# board-alt.net
KiCad netlist of a schematic drawn in EAGLE
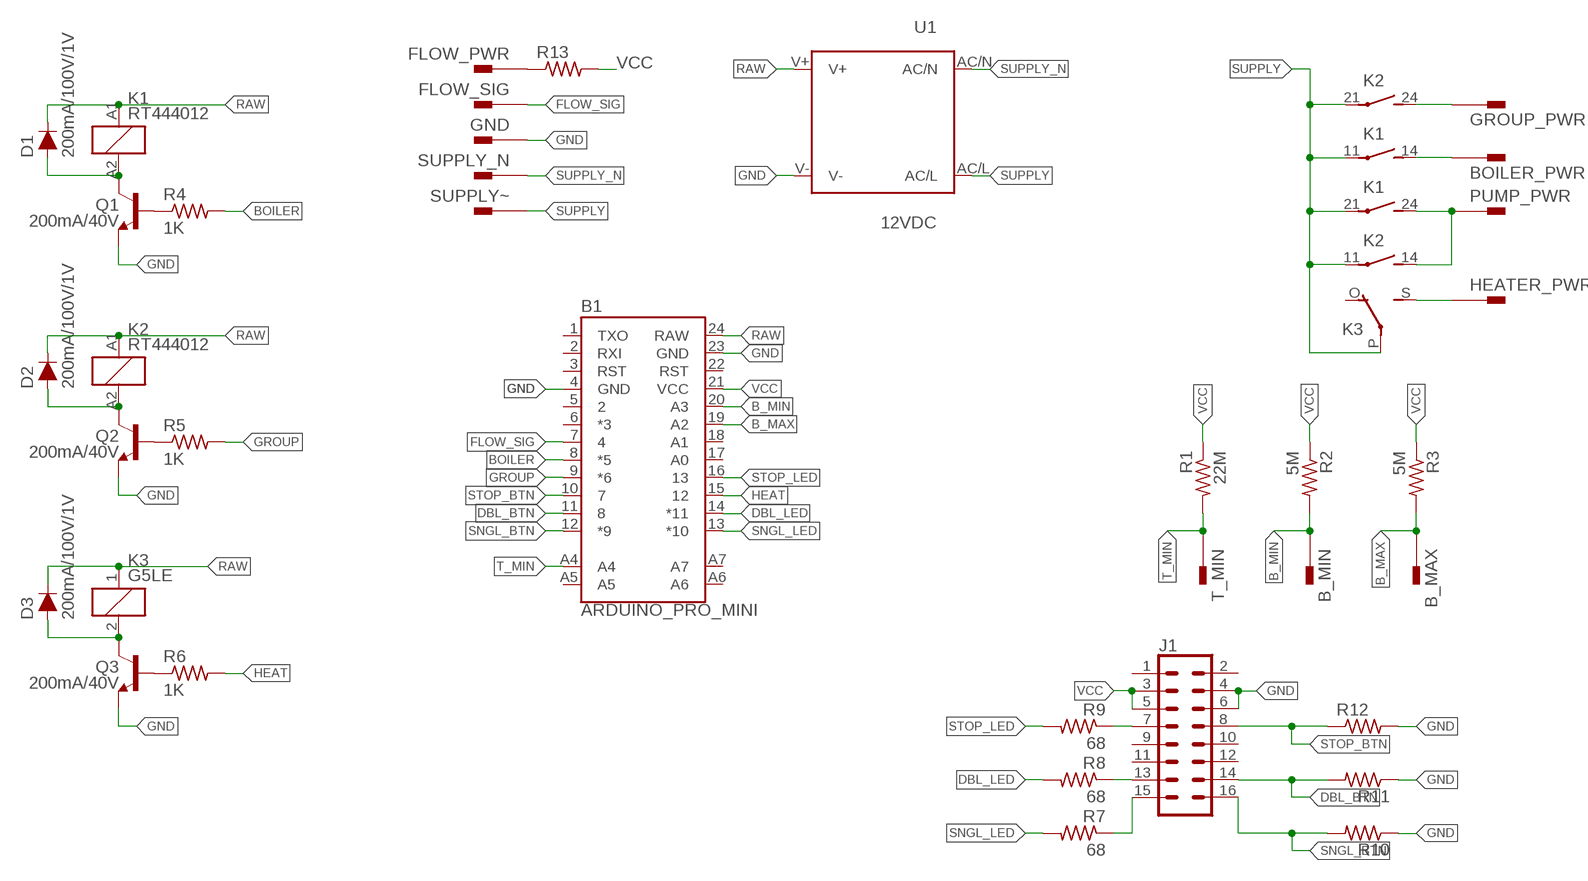
[diagram p0: schematic, sheet 1]

(export (version "E")
  (design (tool "Eeschema 10.0.6"))
  (components
    (comp (ref "B1")
      (value "ARDUINO_PRO_MINI")
      (footprint "eagle-import:ARDUINO_PRO_MINI")
      (libsource (lib "eagle-import") (part "ARDUINO_PRO_MINI"))
    )
    (comp (ref "BOILER_PWR")
      (value "PIN2F061.040")
      (footprint "eagle-import:F061.040")
      (libsource (lib "eagle-import") (part "PIN2F061.040"))
    )
    (comp (ref "B_MAX")
      (value "PIN2F061.040")
      (footprint "eagle-import:F061.040")
      (libsource (lib "eagle-import") (part "PIN2F061.040"))
    )
    (comp (ref "B_MIN")
      (value "PIN2F061.040")
      (footprint "eagle-import:F061.040")
      (libsource (lib "eagle-import") (part "PIN2F061.040"))
    )
    (comp (ref "D1")
      (value "200mA/100V/1V")
      (footprint "eagle-import:DIODE-1N4148")
      (libsource (lib "eagle-import") (part "DIODE-1N4148"))
    )
    (comp (ref "D2")
      (value "200mA/100V/1V")
      (footprint "eagle-import:DIODE-1N4148")
      (libsource (lib "eagle-import") (part "DIODE-1N4148"))
    )
    (comp (ref "D3")
      (value "200mA/100V/1V")
      (footprint "eagle-import:DIODE-1N4148")
      (libsource (lib "eagle-import") (part "DIODE-1N4148"))
    )
    (comp (ref "FLOW_PWR")
      (value "PIN2F061.040")
      (footprint "eagle-import:F061.040")
      (libsource (lib "eagle-import") (part "PIN2F061.040"))
    )
    (comp (ref "FLOW_SIG")
      (value "PIN2F061.040")
      (footprint "eagle-import:F061.040")
      (libsource (lib "eagle-import") (part "PIN2F061.040"))
    )
    (comp (ref "GND")
      (value "PIN2F061.040")
      (footprint "eagle-import:F061.040")
      (libsource (lib "eagle-import") (part "PIN2F061.040"))
    )
    (comp (ref "GROUP_PWR")
      (value "PIN2F061.040")
      (footprint "eagle-import:F061.040")
      (libsource (lib "eagle-import") (part "PIN2F061.040"))
    )
    (comp (ref "HEATER_PWR")
      (value "PIN2F061.040")
      (footprint "eagle-import:F061.040")
      (libsource (lib "eagle-import") (part "PIN2F061.040"))
    )
    (comp (ref "J1")
      (value "CONN_08X2")
      (footprint "eagle-import:2X8")
      (libsource (lib "eagle-import") (part "CONN_08X2"))
    )
    (comp (ref "K1")
      (value "RT444012")
      (footprint "eagle-import:RT2N_O")
      (libsource (lib "eagle-import") (part "RT44?4012"))
    )
    (comp (ref "K2")
      (value "RT444012")
      (footprint "eagle-import:RT2N_O")
      (libsource (lib "eagle-import") (part "RT44?4012"))
    )
    (comp (ref "K3")
      (value "G5LE")
      (footprint "eagle-import:G5LE")
      (libsource (lib "eagle-import") (part "G5LE"))
    )
    (comp (ref "PUMP_PWR")
      (value "PIN2F061.040")
      (footprint "eagle-import:F061.040")
      (libsource (lib "eagle-import") (part "PIN2F061.040"))
    )
    (comp (ref "Q1")
      (value "200mA/40V")
      (footprint "eagle-import:TO-92")
      (libsource (lib "eagle-import") (part "TRANS_NPN-2N3904"))
    )
    (comp (ref "Q2")
      (value "200mA/40V")
      (footprint "eagle-import:TO-92")
      (libsource (lib "eagle-import") (part "TRANS_NPN-2N3904"))
    )
    (comp (ref "Q3")
      (value "200mA/40V")
      (footprint "eagle-import:TO-92")
      (libsource (lib "eagle-import") (part "TRANS_NPN-2N3904"))
    )
    (comp (ref "R1")
      (value "22M")
      (footprint "eagle-import:0207_7")
      (libsource (lib "eagle-import") (part "R-US_0207/7"))
    )
    (comp (ref "R2")
      (value "5M")
      (footprint "eagle-import:0207_7")
      (libsource (lib "eagle-import") (part "R-US_0207/7"))
    )
    (comp (ref "R3")
      (value "5M")
      (footprint "eagle-import:0207_7")
      (libsource (lib "eagle-import") (part "R-US_0207/7"))
    )
    (comp (ref "R4")
      (value "1K")
      (footprint "eagle-import:0207_7")
      (libsource (lib "eagle-import") (part "R-US_0207/7"))
    )
    (comp (ref "R5")
      (value "1K")
      (footprint "eagle-import:0207_7")
      (libsource (lib "eagle-import") (part "R-US_0207/7"))
    )
    (comp (ref "R6")
      (value "1K")
      (footprint "eagle-import:0207_7")
      (libsource (lib "eagle-import") (part "R-US_0207/7"))
    )
    (comp (ref "R7")
      (value "68")
      (footprint "eagle-import:0207_7")
      (libsource (lib "eagle-import") (part "R-US_0207/7"))
    )
    (comp (ref "R8")
      (value "68")
      (footprint "eagle-import:0207_7")
      (libsource (lib "eagle-import") (part "R-US_0207/7"))
    )
    (comp (ref "R9")
      (value "68")
      (footprint "eagle-import:0207_7")
      (libsource (lib "eagle-import") (part "R-US_0207/7"))
    )
    (comp (ref "R10")
      (value "R-US_0207/7")
      (footprint "eagle-import:0207_7")
      (libsource (lib "eagle-import") (part "R-US_0207/7"))
    )
    (comp (ref "R11")
      (value "R-US_0207/7")
      (footprint "eagle-import:0207_7")
      (libsource (lib "eagle-import") (part "R-US_0207/7"))
    )
    (comp (ref "R12")
      (value "R-US_0207/7")
      (footprint "eagle-import:0207_7")
      (libsource (lib "eagle-import") (part "R-US_0207/7"))
    )
    (comp (ref "R13")
      (value "R-US_0207/7")
      (footprint "eagle-import:0207_7")
      (libsource (lib "eagle-import") (part "R-US_0207/7"))
    )
    (comp (ref "SUPPLY_N")
      (value "PIN2F061.040")
      (footprint "eagle-import:F061.040")
      (libsource (lib "eagle-import") (part "PIN2F061.040"))
    )
    (comp (ref "SUPPLY~")
      (value "PIN2F061.040")
      (footprint "eagle-import:F061.040")
      (libsource (lib "eagle-import") (part "PIN2F061.040"))
    )
    (comp (ref "T_MIN")
      (value "PIN2F061.040")
      (footprint "eagle-import:F061.040")
      (libsource (lib "eagle-import") (part "PIN2F061.040"))
    )
    (comp (ref "U1")
      (value "12VDC")
      (footprint "eagle-import:IRM_05_10")
      (libsource (lib "eagle-import") (part "IRM_05/10"))
    )
  )
  (nets
    (net (code "1") (name "BOILER") (class "Default")
      (node (ref "B1") (pin "8") (pinfunction "*5_8") (pintype "bidirectional"))
      (node (ref "R4") (pin "2") (pinfunction "2_2") (pintype "passive"))
    )
    (net (code "2") (name "B_MAX") (class "Default")
      (node (ref "B1") (pin "19") (pinfunction "A2_19") (pintype "bidirectional"))
      (node (ref "B_MAX") (pin "A1") (pinfunction "1_A1") (pintype "passive"))
      (node (ref "B_MAX") (pin "A2") (pinfunction "1_A2") (pintype "passive"))
      (node (ref "R3") (pin "2") (pinfunction "2_2") (pintype "passive"))
    )
    (net (code "3") (name "B_MIN") (class "Default")
      (node (ref "B1") (pin "20") (pinfunction "A3_20") (pintype "bidirectional"))
      (node (ref "B_MIN") (pin "A1") (pinfunction "1_A1") (pintype "passive"))
      (node (ref "B_MIN") (pin "A2") (pinfunction "1_A2") (pintype "passive"))
      (node (ref "R2") (pin "2") (pinfunction "2_2") (pintype "passive"))
    )
    (net (code "4") (name "DBL_BTN") (class "Default")
      (node (ref "B1") (pin "11") (pinfunction "8_11") (pintype "bidirectional"))
      (node (ref "J1") (pin "14") (pinfunction "14_14") (pintype "passive"))
      (node (ref "R11") (pin "2") (pinfunction "2_2") (pintype "passive"))
    )
    (net (code "5") (name "DBL_LED") (class "Default")
      (node (ref "B1") (pin "14") (pinfunction "*11_14") (pintype "bidirectional"))
      (node (ref "R8") (pin "2") (pinfunction "2_2") (pintype "passive"))
    )
    (net (code "6") (name "FLOW_SIG") (class "Default")
      (node (ref "B1") (pin "7") (pinfunction "4_7") (pintype "bidirectional"))
      (node (ref "FLOW_SIG") (pin "A1") (pinfunction "1_A1") (pintype "passive"))
      (node (ref "FLOW_SIG") (pin "A2") (pinfunction "1_A2") (pintype "passive"))
    )
    (net (code "7") (name "GND") (class "Default")
      (node (ref "B1") (pin "23") (pinfunction "GND_23") (pintype "power_in"))
      (node (ref "B1") (pin "4") (pinfunction "GND_4") (pintype "power_in"))
      (node (ref "GND") (pin "A1") (pinfunction "1_A1") (pintype "passive"))
      (node (ref "GND") (pin "A2") (pinfunction "1_A2") (pintype "passive"))
      (node (ref "J1") (pin "4") (pinfunction "4_4") (pintype "passive"))
      (node (ref "J1") (pin "6") (pinfunction "6_6") (pintype "passive"))
      (node (ref "Q1") (pin "1") (pinfunction "E_1") (pintype "passive"))
      (node (ref "Q2") (pin "1") (pinfunction "E_1") (pintype "passive"))
      (node (ref "Q3") (pin "1") (pinfunction "E_1") (pintype "passive"))
      (node (ref "R10") (pin "1") (pinfunction "1_1") (pintype "passive"))
      (node (ref "R11") (pin "1") (pinfunction "1_1") (pintype "passive"))
      (node (ref "R12") (pin "2") (pinfunction "2_2") (pintype "passive"))
      (node (ref "U1") (pin "V-") (pinfunction "V-_V-") (pintype "output"))
    )
    (net (code "8") (name "GROUP") (class "Default")
      (node (ref "B1") (pin "9") (pinfunction "*6_9") (pintype "bidirectional"))
      (node (ref "R5") (pin "2") (pinfunction "2_2") (pintype "passive"))
    )
    (net (code "9") (name "HEAT") (class "Default")
      (node (ref "B1") (pin "15") (pinfunction "12_15") (pintype "bidirectional"))
      (node (ref "R6") (pin "2") (pinfunction "2_2") (pintype "passive"))
    )
    (net (code "10") (name "Net-(FLOW_PWR-1-PadA1)") (class "Default")
      (node (ref "FLOW_PWR") (pin "A1") (pinfunction "1_A1") (pintype "passive"))
      (node (ref "FLOW_PWR") (pin "A2") (pinfunction "1_A2") (pintype "passive"))
      (node (ref "R13") (pin "1") (pinfunction "1_1") (pintype "passive"))
    )
    (net (code "11") (name "Net-(HEATER_PWR-1-PadA1)") (class "Default")
      (node (ref "HEATER_PWR") (pin "A1") (pinfunction "1_A1") (pintype "passive"))
      (node (ref "HEATER_PWR") (pin "A2") (pinfunction "1_A2") (pintype "passive"))
      (node (ref "K3") (pin "S") (pinfunction "S_S") (pintype "passive"))
    )
    (net (code "12") (name "Net-(J1-Pad7)") (class "Default")
      (node (ref "J1") (pin "7") (pinfunction "7_7") (pintype "passive"))
      (node (ref "R9") (pin "1") (pinfunction "1_1") (pintype "passive"))
    )
    (net (code "13") (name "Net-(J1-Pad13)") (class "Default")
      (node (ref "J1") (pin "13") (pinfunction "13_13") (pintype "passive"))
      (node (ref "R8") (pin "1") (pinfunction "1_1") (pintype "passive"))
    )
    (net (code "14") (name "Net-(J1-Pad15)") (class "Default")
      (node (ref "J1") (pin "15") (pinfunction "15_15") (pintype "passive"))
      (node (ref "R7") (pin "1") (pinfunction "1_1") (pintype "passive"))
    )
    (net (code "15") (name "Net-(K1A-2)") (class "Default")
      (node (ref "D1") (pin "A") (pinfunction "A_A") (pintype "passive"))
      (node (ref "K1") (pin "A2") (pinfunction "2_A2") (pintype "passive"))
      (node (ref "Q1") (pin "3") (pinfunction "C_3") (pintype "passive"))
    )
    (net (code "16") (name "Net-(K1B-S)") (class "Default")
      (node (ref "BOILER_PWR") (pin "A1") (pinfunction "1_A1") (pintype "passive"))
      (node (ref "BOILER_PWR") (pin "A2") (pinfunction "1_A2") (pintype "passive"))
      (node (ref "K1") (pin "14") (pinfunction "S_14") (pintype "passive"))
    )
    (net (code "17") (name "Net-(K1C-S)") (class "Default")
      (node (ref "K1") (pin "24") (pinfunction "S_24") (pintype "passive"))
      (node (ref "K2") (pin "14") (pinfunction "S_14") (pintype "passive"))
      (node (ref "PUMP_PWR") (pin "A1") (pinfunction "1_A1") (pintype "passive"))
      (node (ref "PUMP_PWR") (pin "A2") (pinfunction "1_A2") (pintype "passive"))
    )
    (net (code "18") (name "Net-(K2A-2)") (class "Default")
      (node (ref "D2") (pin "A") (pinfunction "A_A") (pintype "passive"))
      (node (ref "K2") (pin "A2") (pinfunction "2_A2") (pintype "passive"))
      (node (ref "Q2") (pin "3") (pinfunction "C_3") (pintype "passive"))
    )
    (net (code "19") (name "Net-(K2C-S)") (class "Default")
      (node (ref "GROUP_PWR") (pin "A1") (pinfunction "1_A1") (pintype "passive"))
      (node (ref "GROUP_PWR") (pin "A2") (pinfunction "1_A2") (pintype "passive"))
      (node (ref "K2") (pin "24") (pinfunction "S_24") (pintype "passive"))
    )
    (net (code "20") (name "Net-(Q1-B)") (class "Default")
      (node (ref "Q1") (pin "2") (pinfunction "B_2") (pintype "passive"))
      (node (ref "R4") (pin "1") (pinfunction "1_1") (pintype "passive"))
    )
    (net (code "21") (name "Net-(Q2-B)") (class "Default")
      (node (ref "Q2") (pin "2") (pinfunction "B_2") (pintype "passive"))
      (node (ref "R5") (pin "1") (pinfunction "1_1") (pintype "passive"))
    )
    (net (code "22") (name "Net-(Q3-B)") (class "Default")
      (node (ref "Q3") (pin "2") (pinfunction "B_2") (pintype "passive"))
      (node (ref "R6") (pin "1") (pinfunction "1_1") (pintype "passive"))
    )
    (net (code "23") (name "Net-(Q3-C)") (class "Default")
      (node (ref "D3") (pin "A") (pinfunction "A_A") (pintype "passive"))
      (node (ref "K3") (pin "2") (pinfunction "2_2") (pintype "passive"))
      (node (ref "Q3") (pin "3") (pinfunction "C_3") (pintype "passive"))
    )
    (net (code "24") (name "RAW") (class "Default")
      (node (ref "B1") (pin "24") (pinfunction "RAW_24") (pintype "power_in"))
      (node (ref "D1") (pin "C") (pinfunction "C_C") (pintype "passive"))
      (node (ref "D2") (pin "C") (pinfunction "C_C") (pintype "passive"))
      (node (ref "D3") (pin "C") (pinfunction "C_C") (pintype "passive"))
      (node (ref "K1") (pin "A1") (pinfunction "1_A1") (pintype "passive"))
      (node (ref "K2") (pin "A1") (pinfunction "1_A1") (pintype "passive"))
      (node (ref "K3") (pin "1") (pinfunction "1_1") (pintype "passive"))
      (node (ref "U1") (pin "V+") (pinfunction "V+_V+") (pintype "output"))
    )
    (net (code "25") (name "SNGL_BTN") (class "Default")
      (node (ref "B1") (pin "12") (pinfunction "*9_12") (pintype "bidirectional"))
      (node (ref "J1") (pin "16") (pinfunction "16_16") (pintype "passive"))
      (node (ref "R10") (pin "2") (pinfunction "2_2") (pintype "passive"))
    )
    (net (code "26") (name "SNGL_LED") (class "Default")
      (node (ref "B1") (pin "13") (pinfunction "*10_13") (pintype "bidirectional"))
      (node (ref "R7") (pin "2") (pinfunction "2_2") (pintype "passive"))
    )
    (net (code "27") (name "STOP_BTN") (class "Default")
      (node (ref "B1") (pin "10") (pinfunction "7_10") (pintype "bidirectional"))
      (node (ref "J1") (pin "8") (pinfunction "8_8") (pintype "passive"))
      (node (ref "R12") (pin "1") (pinfunction "1_1") (pintype "passive"))
    )
    (net (code "28") (name "STOP_LED") (class "Default")
      (node (ref "B1") (pin "16") (pinfunction "13_16") (pintype "bidirectional"))
      (node (ref "R9") (pin "2") (pinfunction "2_2") (pintype "passive"))
    )
    (net (code "29") (name "SUPPLY") (class "Default")
      (node (ref "K1") (pin "11") (pinfunction "P_11") (pintype "passive"))
      (node (ref "K1") (pin "21") (pinfunction "P_21") (pintype "passive"))
      (node (ref "K2") (pin "11") (pinfunction "P_11") (pintype "passive"))
      (node (ref "K2") (pin "21") (pinfunction "P_21") (pintype "passive"))
      (node (ref "K3") (pin "P") (pinfunction "P_P") (pintype "passive"))
      (node (ref "SUPPLY~") (pin "A1") (pinfunction "1_A1") (pintype "passive"))
      (node (ref "SUPPLY~") (pin "A2") (pinfunction "1_A2") (pintype "passive"))
      (node (ref "U1") (pin "AC/L") (pinfunction "AC/L_AC/L") (pintype "input"))
    )
    (net (code "30") (name "SUPPLY_N") (class "Default")
      (node (ref "SUPPLY_N") (pin "A1") (pinfunction "1_A1") (pintype "passive"))
      (node (ref "SUPPLY_N") (pin "A2") (pinfunction "1_A2") (pintype "passive"))
      (node (ref "U1") (pin "AC/N") (pinfunction "AC/N_AC/N") (pintype "input"))
    )
    (net (code "31") (name "T_MIN") (class "Default")
      (node (ref "B1") (pin "A4") (pinfunction "A4_A4") (pintype "bidirectional"))
      (node (ref "R1") (pin "2") (pinfunction "2_2") (pintype "passive"))
      (node (ref "T_MIN") (pin "A1") (pinfunction "1_A1") (pintype "passive"))
      (node (ref "T_MIN") (pin "A2") (pinfunction "1_A2") (pintype "passive"))
    )
    (net (code "32") (name "VCC") (class "Default")
      (node (ref "B1") (pin "21") (pinfunction "VCC_21") (pintype "power_in"))
      (node (ref "J1") (pin "3") (pinfunction "3_3") (pintype "passive"))
      (node (ref "J1") (pin "5") (pinfunction "5_5") (pintype "passive"))
      (node (ref "R1") (pin "1") (pinfunction "1_1") (pintype "passive"))
      (node (ref "R13") (pin "2") (pinfunction "2_2") (pintype "passive"))
      (node (ref "R2") (pin "1") (pinfunction "1_1") (pintype "passive"))
      (node (ref "R3") (pin "1") (pinfunction "1_1") (pintype "passive"))
    )
    (net (code "33") (name "unconnected-(B1-*3-Pad6)") (class "Default")
      (node (ref "B1") (pin "6") (pinfunction "*3_6") (pintype "bidirectional"))
    )
    (net (code "34") (name "unconnected-(B1-2-Pad5)") (class "Default")
      (node (ref "B1") (pin "5") (pinfunction "2_5") (pintype "bidirectional"))
    )
    (net (code "35") (name "unconnected-(B1-A0-Pad17)") (class "Default")
      (node (ref "B1") (pin "17") (pinfunction "A0_17") (pintype "bidirectional"))
    )
    (net (code "36") (name "unconnected-(B1-A1-Pad18)") (class "Default")
      (node (ref "B1") (pin "18") (pinfunction "A1_18") (pintype "bidirectional"))
    )
    (net (code "37") (name "unconnected-(B1-PadA5)") (class "Default")
      (node (ref "B1") (pin "A5") (pinfunction "A5_A5") (pintype "bidirectional"))
    )
    (net (code "38") (name "unconnected-(B1-PadA6)") (class "Default")
      (node (ref "B1") (pin "A6") (pinfunction "A6_A6") (pintype "bidirectional"))
    )
    (net (code "39") (name "unconnected-(B1-PadA7)") (class "Default")
      (node (ref "B1") (pin "A7") (pinfunction "A7_A7") (pintype "bidirectional"))
    )
    (net (code "40") (name "unconnected-(B1-RST-Pad3)") (class "Default")
      (node (ref "B1") (pin "3") (pinfunction "RST_3") (pintype "bidirectional"))
    )
    (net (code "41") (name "unconnected-(B1-RST-Pad22)") (class "Default")
      (node (ref "B1") (pin "22") (pinfunction "RST_22") (pintype "bidirectional"))
    )
    (net (code "42") (name "unconnected-(B1-RXI-Pad2)") (class "Default")
      (node (ref "B1") (pin "2") (pinfunction "RXI_2") (pintype "bidirectional"))
    )
    (net (code "43") (name "unconnected-(B1-TXO-Pad1)") (class "Default")
      (node (ref "B1") (pin "1") (pinfunction "TXO_1") (pintype "bidirectional"))
    )
    (net (code "44") (name "unconnected-(J1-Pad1)") (class "Default")
      (node (ref "J1") (pin "1") (pinfunction "1_1") (pintype "passive"))
    )
    (net (code "45") (name "unconnected-(J1-Pad2)") (class "Default")
      (node (ref "J1") (pin "2") (pinfunction "2_2") (pintype "passive"))
    )
    (net (code "46") (name "unconnected-(J1-Pad9)") (class "Default")
      (node (ref "J1") (pin "9") (pinfunction "9_9") (pintype "passive"))
    )
    (net (code "47") (name "unconnected-(J1-Pad10)") (class "Default")
      (node (ref "J1") (pin "10") (pinfunction "10_10") (pintype "passive"))
    )
    (net (code "48") (name "unconnected-(J1-Pad11)") (class "Default")
      (node (ref "J1") (pin "11") (pinfunction "11_11") (pintype "passive"))
    )
    (net (code "49") (name "unconnected-(J1-Pad12)") (class "Default")
      (node (ref "J1") (pin "12") (pinfunction "12_12") (pintype "passive"))
    )
    (net (code "50") (name "unconnected-(K3-PadO)") (class "Default")
      (node (ref "K3") (pin "O") (pinfunction "O_O") (pintype "passive"))
    )
  )
)
